# FinalSchematic1_2.net
KiCad netlist of a schematic drawn in EAGLE
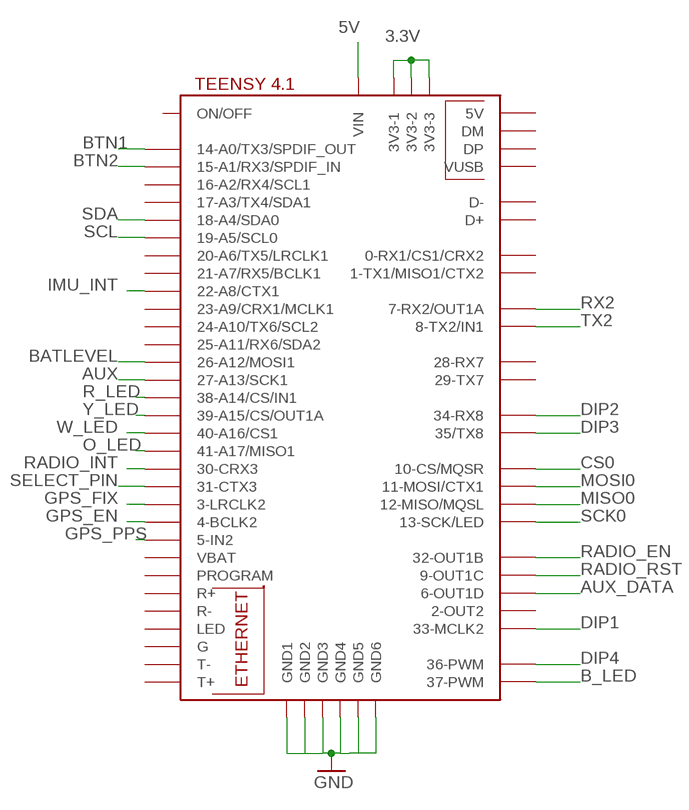
[diagram p0: schematic, sheet 1]
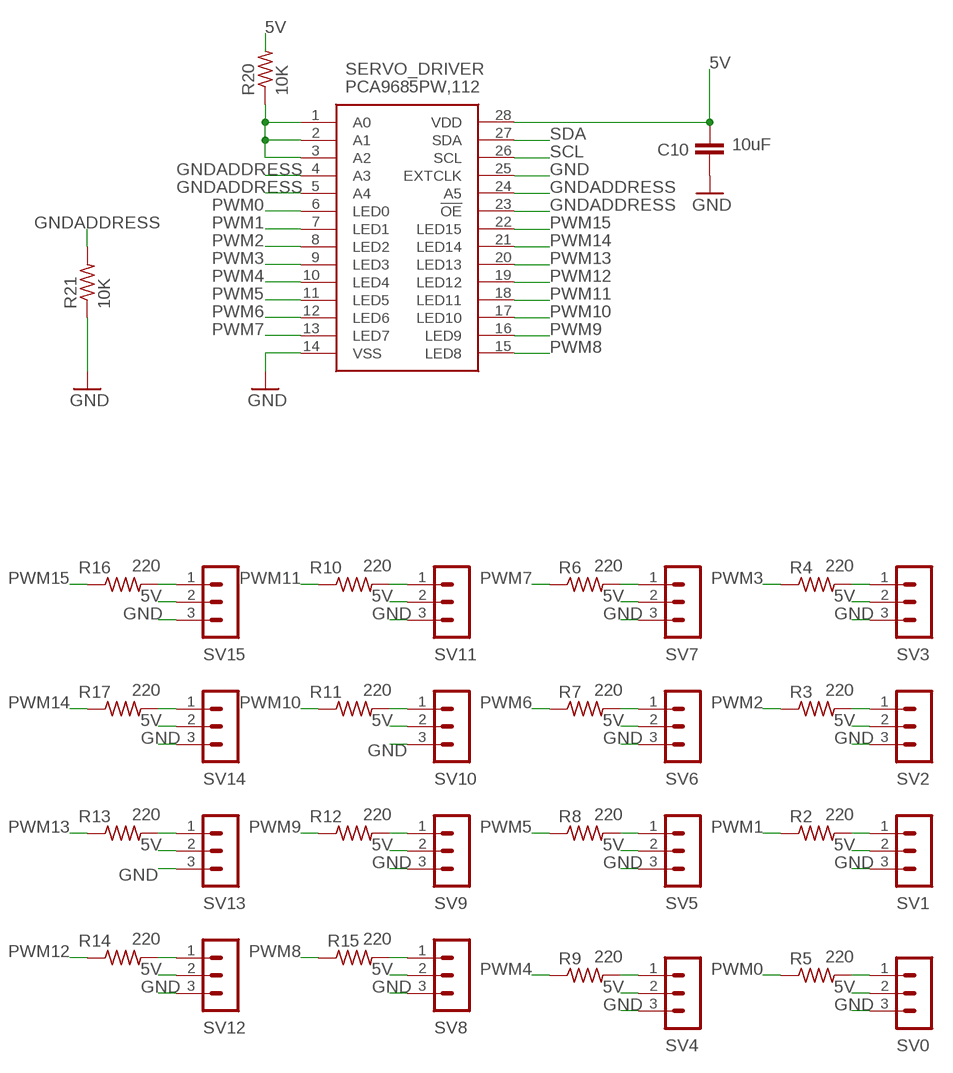
[diagram p1: schematic, sheet 2]
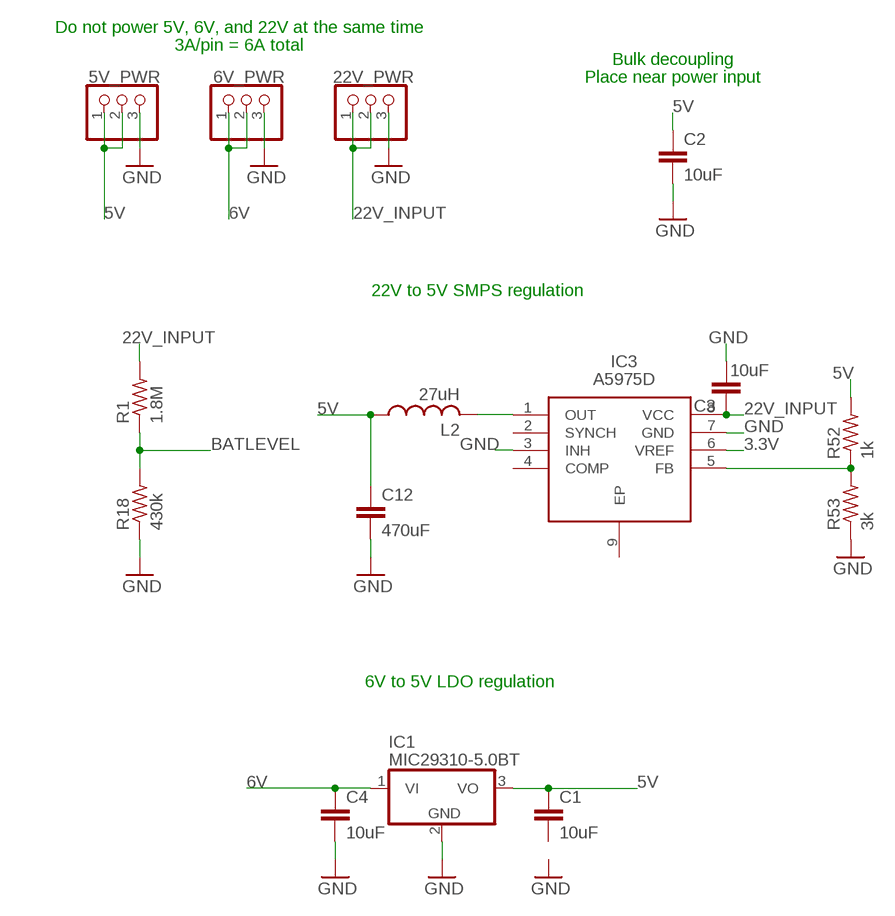
[diagram p2: schematic, sheet 3]
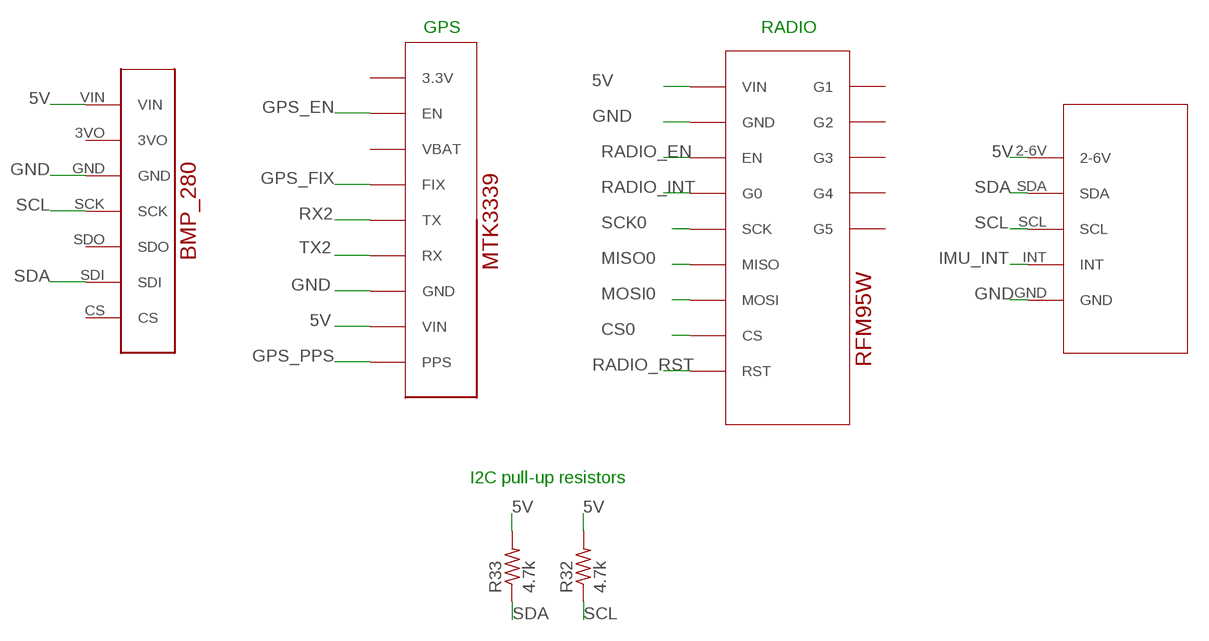
[diagram p3: schematic, sheet 4]
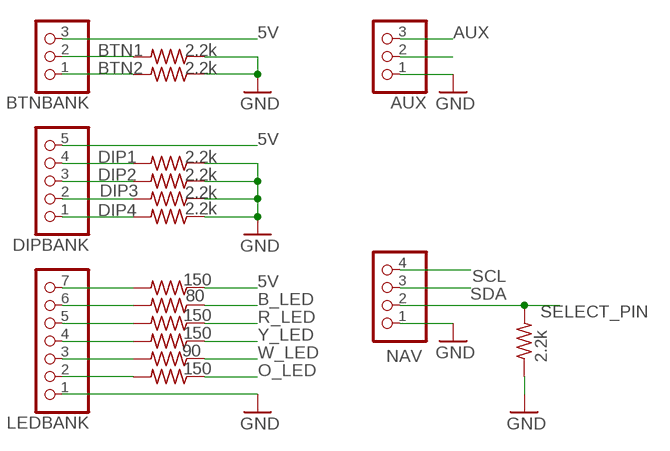
[diagram p4: schematic, sheet 5]
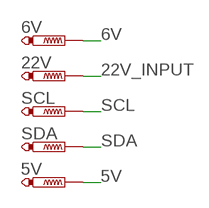
[diagram p5: schematic, sheet 6]

(export (version "E")
  (design (tool "Eeschema 10.0.6"))
  (components
    (comp (ref "TEENSY4.1")
      (value "TEENSY41")
      (footprint "eagle-import:TEENSY41")
      (libsource (lib "eagle-import") (part "TEENSY41"))
    )
    (comp (ref "5V")
      (value "PTR1B1,27")
      (footprint "eagle-import:B1,27")
      (libsource (lib "eagle-import") (part "PTR1B1,27"))
    )
    (comp (ref "6V")
      (value "PTR1B1,27")
      (footprint "eagle-import:B1,27")
      (libsource (lib "eagle-import") (part "PTR1B1,27"))
    )
    (comp (ref "22V")
      (value "PTR1B1,27")
      (footprint "eagle-import:B1,27")
      (libsource (lib "eagle-import") (part "PTR1B1,27"))
    )
    (comp (ref "SCL")
      (value "PTR1B1,27")
      (footprint "eagle-import:B1,27")
      (libsource (lib "eagle-import") (part "PTR1B1,27"))
    )
    (comp (ref "SDA")
      (value "PTR1B1,27")
      (footprint "eagle-import:B1,27")
      (libsource (lib "eagle-import") (part "PTR1B1,27"))
    )
    (comp (ref "AUX")
      (value "PINHD-1X3")
      (footprint "eagle-import:1X03")
      (libsource (lib "eagle-import") (part "PINHD-1X3"))
    )
    (comp (ref "BLUE")
      (value "80")
      (footprint "eagle-import:0204_7")
      (libsource (lib "eagle-import") (part "R-US_0204/7"))
    )
    (comp (ref "BTNBANK")
      (value "PINHD-1X3")
      (footprint "eagle-import:1X03")
      (libsource (lib "eagle-import") (part "PINHD-1X3"))
    )
    (comp (ref "DIPBANK")
      (value "PINHD-1X5")
      (footprint "eagle-import:1X05")
      (libsource (lib "eagle-import") (part "PINHD-1X5"))
    )
    (comp (ref "GREEN")
      (value "150")
      (footprint "eagle-import:0204_7")
      (libsource (lib "eagle-import") (part "R-US_0204/7"))
    )
    (comp (ref "LEDBANK")
      (value "PINHD-1X7")
      (footprint "eagle-import:1X07")
      (libsource (lib "eagle-import") (part "PINHD-1X7"))
    )
    (comp (ref "NAV")
      (value "PINHD-1X4")
      (footprint "eagle-import:1X04")
      (libsource (lib "eagle-import") (part "PINHD-1X4"))
    )
    (comp (ref "ORANGE")
      (value "150")
      (footprint "eagle-import:0204_7")
      (libsource (lib "eagle-import") (part "R-US_0204/7"))
    )
    (comp (ref "R19")
      (value "2.2k")
      (footprint "eagle-import:0204_7")
      (libsource (lib "eagle-import") (part "R-US_0204/7"))
    )
    (comp (ref "R22")
      (value "2.2k")
      (footprint "eagle-import:0204_7")
      (libsource (lib "eagle-import") (part "R-US_0204/7"))
    )
    (comp (ref "R23")
      (value "2.2k")
      (footprint "eagle-import:0204_7")
      (libsource (lib "eagle-import") (part "R-US_0204/7"))
    )
    (comp (ref "R34")
      (value "2.2k")
      (footprint "eagle-import:0204_7")
      (libsource (lib "eagle-import") (part "R-US_0204/7"))
    )
    (comp (ref "R35")
      (value "2.2k")
      (footprint "eagle-import:0204_7")
      (libsource (lib "eagle-import") (part "R-US_0204/7"))
    )
    (comp (ref "R36")
      (value "2.2k")
      (footprint "eagle-import:0204_7")
      (libsource (lib "eagle-import") (part "R-US_0204/7"))
    )
    (comp (ref "R37")
      (value "2.2k")
      (footprint "eagle-import:0204_7")
      (libsource (lib "eagle-import") (part "R-US_0204/7"))
    )
    (comp (ref "RED")
      (value "150")
      (footprint "eagle-import:0204_7")
      (libsource (lib "eagle-import") (part "R-US_0204/7"))
    )
    (comp (ref "WHITE")
      (value "90")
      (footprint "eagle-import:0204_7")
      (libsource (lib "eagle-import") (part "R-US_0204/7"))
    )
    (comp (ref "YELLOW")
      (value "150")
      (footprint "eagle-import:0204_7")
      (libsource (lib "eagle-import") (part "R-US_0204/7"))
    )
    (comp (ref "5V_PWR")
      (value "PINHD-1X3")
      (footprint "eagle-import:1X03")
      (libsource (lib "eagle-import") (part "PINHD-1X3"))
    )
    (comp (ref "6V_PWR")
      (value "PINHD-1X3")
      (footprint "eagle-import:1X03")
      (libsource (lib "eagle-import") (part "PINHD-1X3"))
    )
    (comp (ref "22V_PWR")
      (value "PINHD-1X3")
      (footprint "eagle-import:1X03")
      (libsource (lib "eagle-import") (part "PINHD-1X3"))
    )
    (comp (ref "C1")
      (value "10uF")
      (footprint "eagle-import:C2.5-3")
      (libsource (lib "eagle-import") (part "C2,5-3"))
    )
    (comp (ref "C2")
      (value "10uF")
      (footprint "eagle-import:C2.5-3")
      (libsource (lib "eagle-import") (part "C2,5-3"))
    )
    (comp (ref "C3")
      (value "10uF")
      (footprint "eagle-import:C2.5-3")
      (libsource (lib "eagle-import") (part "C2,5-3"))
    )
    (comp (ref "C4")
      (value "10uF")
      (footprint "eagle-import:C2.5-3")
      (libsource (lib "eagle-import") (part "C2,5-3"))
    )
    (comp (ref "C12")
      (value "470uF")
      (footprint "eagle-import:C2.5-3")
      (libsource (lib "eagle-import") (part "C2,5-3"))
    )
    (comp (ref "IC1")
      (value "MIC29310-5.0BT")
      (footprint "eagle-import:TO220V")
      (libsource (lib "eagle-import") (part "78TV6"))
    )
    (comp (ref "IC3")
      (value "A5975D")
      (footprint "eagle-import:SOIC127P600X170-9N")
      (fields (field (name "MOUSER_PART_NUMBER") "511-A5975D"))
      (libsource (lib "eagle-import") (part "A5975D"))
    )
    (comp (ref "L2")
      (value "27uH")
      (footprint "eagle-import:TFI0307")
      (libsource (lib "eagle-import") (part "L-USTFI0307"))
    )
    (comp (ref "R1")
      (value "1.8M")
      (footprint "eagle-import:0204_7")
      (libsource (lib "eagle-import") (part "R-US_0204/7"))
    )
    (comp (ref "R18")
      (value "430k")
      (footprint "eagle-import:0204_7")
      (libsource (lib "eagle-import") (part "R-US_0204/7"))
    )
    (comp (ref "R52")
      (value "1k")
      (footprint "eagle-import:0204_7")
      (libsource (lib "eagle-import") (part "R-US_0204/7"))
    )
    (comp (ref "R53")
      (value "3k")
      (footprint "eagle-import:0204_7")
      (libsource (lib "eagle-import") (part "R-US_0204/7"))
    )
    (comp (ref "GPSMTK3339")
      (value "ADAFRUIT_MTK3339_GPS")
      (footprint "eagle-import:ADAFRUIT_MTK3339_GPS")
      (libsource (lib "eagle-import") (part "ADAFRUIT_MTK3339_GPS"))
    )
    (comp (ref "IMU")
      (value "ICM20948BREAKOUTDEVICE")
      (footprint "eagle-import:ICM20948BREAKOUT")
      (fields (field (name "SPICEPREFIX") "X"))
      (libsource (lib "eagle-import") (part "ICM20948BREAKOUTDEVICE"))
    )
    (comp (ref "R32")
      (value "4.7k")
      (footprint "eagle-import:0204_7")
      (libsource (lib "eagle-import") (part "R-US_0204/7"))
    )
    (comp (ref "R33")
      (value "4.7k")
      (footprint "eagle-import:0204_7")
      (libsource (lib "eagle-import") (part "R-US_0204/7"))
    )
    (comp (ref "RADIO")
      (value "ADAFRUIT_RFM95W_LORA_RADIO")
      (footprint "eagle-import:ADAFRUIT_RFM95W_LORA_RADIO")
      (libsource (lib "eagle-import") (part "ADAFRUIT_RFM95W_LORA_RADIO"))
    )
    (comp (ref "U1")
      (value "ADAFRUIT_BMP280_BAROMETER")
      (footprint "eagle-import:ADAFRUIT_BMP280_BAROMETER")
      (libsource (lib "eagle-import") (part "ADAFRUIT_BMP280_BAROMETER"))
    )
    (comp (ref "C10")
      (value "10uF")
      (footprint "eagle-import:C2.5-3")
      (libsource (lib "eagle-import") (part "C2,5-3"))
    )
    (comp (ref "R2")
      (value "220")
      (footprint "eagle-import:0204_7")
      (libsource (lib "eagle-import") (part "R-US_0204/7"))
    )
    (comp (ref "R3")
      (value "220")
      (footprint "eagle-import:0204_7")
      (libsource (lib "eagle-import") (part "R-US_0204/7"))
    )
    (comp (ref "R4")
      (value "220")
      (footprint "eagle-import:0204_7")
      (libsource (lib "eagle-import") (part "R-US_0204/7"))
    )
    (comp (ref "R5")
      (value "220")
      (footprint "eagle-import:0204_7")
      (libsource (lib "eagle-import") (part "R-US_0204/7"))
    )
    (comp (ref "R6")
      (value "220")
      (footprint "eagle-import:0204_7")
      (libsource (lib "eagle-import") (part "R-US_0204/7"))
    )
    (comp (ref "R7")
      (value "220")
      (footprint "eagle-import:0204_7")
      (libsource (lib "eagle-import") (part "R-US_0204/7"))
    )
    (comp (ref "R8")
      (value "220")
      (footprint "eagle-import:0204_7")
      (libsource (lib "eagle-import") (part "R-US_0204/7"))
    )
    (comp (ref "R9")
      (value "220")
      (footprint "eagle-import:0204_7")
      (libsource (lib "eagle-import") (part "R-US_0204/7"))
    )
    (comp (ref "R10")
      (value "220")
      (footprint "eagle-import:0204_7")
      (libsource (lib "eagle-import") (part "R-US_0204/7"))
    )
    (comp (ref "R11")
      (value "220")
      (footprint "eagle-import:0204_7")
      (libsource (lib "eagle-import") (part "R-US_0204/7"))
    )
    (comp (ref "R12")
      (value "220")
      (footprint "eagle-import:0204_7")
      (libsource (lib "eagle-import") (part "R-US_0204/7"))
    )
    (comp (ref "R13")
      (value "220")
      (footprint "eagle-import:0204_7")
      (libsource (lib "eagle-import") (part "R-US_0204/7"))
    )
    (comp (ref "R14")
      (value "220")
      (footprint "eagle-import:0204_7")
      (libsource (lib "eagle-import") (part "R-US_0204/7"))
    )
    (comp (ref "R15")
      (value "220")
      (footprint "eagle-import:0204_7")
      (libsource (lib "eagle-import") (part "R-US_0204/7"))
    )
    (comp (ref "R16")
      (value "220")
      (footprint "eagle-import:0204_7")
      (libsource (lib "eagle-import") (part "R-US_0204/7"))
    )
    (comp (ref "R17")
      (value "220")
      (footprint "eagle-import:0204_7")
      (libsource (lib "eagle-import") (part "R-US_0204/7"))
    )
    (comp (ref "R20")
      (value "10K")
      (footprint "eagle-import:0204_7")
      (libsource (lib "eagle-import") (part "R-US_0204/7"))
    )
    (comp (ref "R21")
      (value "10K")
      (footprint "eagle-import:0204_7")
      (libsource (lib "eagle-import") (part "R-US_0204/7"))
    )
    (comp (ref "SERVO_DRIVER")
      (value "PCA9685PW,112")
      (footprint "eagle-import:SOP65P640X110-28N")
      (fields (field (name "MOUSER_PART_NUMBER") "771-PCA9685PW,112"))
      (libsource (lib "eagle-import") (part "PCA9685PW,112"))
    )
    (comp (ref "SV0")
      (value "MA03-1")
      (footprint "eagle-import:MA03-1")
      (libsource (lib "eagle-import") (part "MA03-1"))
    )
    (comp (ref "SV1")
      (value "MA03-1")
      (footprint "eagle-import:MA03-1")
      (libsource (lib "eagle-import") (part "MA03-1"))
    )
    (comp (ref "SV2")
      (value "MA03-1")
      (footprint "eagle-import:MA03-1")
      (libsource (lib "eagle-import") (part "MA03-1"))
    )
    (comp (ref "SV3")
      (value "MA03-1")
      (footprint "eagle-import:MA03-1")
      (libsource (lib "eagle-import") (part "MA03-1"))
    )
    (comp (ref "SV4")
      (value "MA03-1")
      (footprint "eagle-import:MA03-1")
      (libsource (lib "eagle-import") (part "MA03-1"))
    )
    (comp (ref "SV5")
      (value "MA03-1")
      (footprint "eagle-import:MA03-1")
      (libsource (lib "eagle-import") (part "MA03-1"))
    )
    (comp (ref "SV6")
      (value "MA03-1")
      (footprint "eagle-import:MA03-1")
      (libsource (lib "eagle-import") (part "MA03-1"))
    )
    (comp (ref "SV7")
      (value "MA03-1")
      (footprint "eagle-import:MA03-1")
      (libsource (lib "eagle-import") (part "MA03-1"))
    )
    (comp (ref "SV8")
      (value "MA03-1")
      (footprint "eagle-import:MA03-1")
      (libsource (lib "eagle-import") (part "MA03-1"))
    )
    (comp (ref "SV9")
      (value "MA03-1")
      (footprint "eagle-import:MA03-1")
      (libsource (lib "eagle-import") (part "MA03-1"))
    )
    (comp (ref "SV10")
      (value "MA03-1")
      (footprint "eagle-import:MA03-1")
      (libsource (lib "eagle-import") (part "MA03-1"))
    )
    (comp (ref "SV11")
      (value "MA03-1")
      (footprint "eagle-import:MA03-1")
      (libsource (lib "eagle-import") (part "MA03-1"))
    )
    (comp (ref "SV12")
      (value "MA03-1")
      (footprint "eagle-import:MA03-1")
      (libsource (lib "eagle-import") (part "MA03-1"))
    )
    (comp (ref "SV13")
      (value "MA03-1")
      (footprint "eagle-import:MA03-1")
      (libsource (lib "eagle-import") (part "MA03-1"))
    )
    (comp (ref "SV14")
      (value "MA03-1")
      (footprint "eagle-import:MA03-1")
      (libsource (lib "eagle-import") (part "MA03-1"))
    )
    (comp (ref "SV15")
      (value "MA03-1")
      (footprint "eagle-import:MA03-1")
      (libsource (lib "eagle-import") (part "MA03-1"))
    )
  )
  (nets
    (net (code "1") (name "3.3V") (class "Default")
      (node (ref "IC3") (pin "6") (pinfunction "VREF_6") (pintype "bidirectional"))
      (node (ref "TEENSY4.1") (pin "3V3-1") (pinfunction "3V3-1_3V3-1") (pintype "bidirectional"))
      (node (ref "TEENSY4.1") (pin "3V3-2") (pinfunction "3V3-2_3V3-2") (pintype "bidirectional"))
      (node (ref "TEENSY4.1") (pin "3V3-3") (pinfunction "3V3-3_3V3-3") (pintype "bidirectional"))
    )
    (net (code "2") (name "5V") (class "Default")
      (node (ref "5V") (pin "TP") (pinfunction "TP_TP") (pintype "input"))
      (node (ref "5V_PWR") (pin "1") (pinfunction "1_1") (pintype "passive"))
      (node (ref "5V_PWR") (pin "2") (pinfunction "2_2") (pintype "passive"))
      (node (ref "BTNBANK") (pin "3") (pinfunction "3_3") (pintype "passive"))
      (node (ref "C1") (pin "1") (pinfunction "1_1") (pintype "passive"))
      (node (ref "C10") (pin "1") (pinfunction "1_1") (pintype "passive"))
      (node (ref "C12") (pin "1") (pinfunction "1_1") (pintype "passive"))
      (node (ref "C2") (pin "1") (pinfunction "1_1") (pintype "passive"))
      (node (ref "DIPBANK") (pin "5") (pinfunction "5_5") (pintype "passive"))
      (node (ref "GPSMTK3339") (pin "VIN") (pinfunction "VIN_VIN") (pintype "bidirectional"))
      (node (ref "GREEN") (pin "1") (pinfunction "1_1") (pintype "passive"))
      (node (ref "IC1") (pin "3") (pinfunction "VO_3") (pintype "passive"))
      (node (ref "IMU") (pin "2-6V") (pinfunction "2-6V_2-6V") (pintype "bidirectional"))
      (node (ref "L2") (pin "1") (pinfunction "1_1") (pintype "passive"))
      (node (ref "R20") (pin "2") (pinfunction "2_2") (pintype "passive"))
      (node (ref "R32") (pin "2") (pinfunction "2_2") (pintype "passive"))
      (node (ref "R33") (pin "2") (pinfunction "2_2") (pintype "passive"))
      (node (ref "R52") (pin "2") (pinfunction "2_2") (pintype "passive"))
      (node (ref "RADIO") (pin "1") (pinfunction "VIN_1") (pintype "bidirectional"))
      (node (ref "SERVO_DRIVER") (pin "28") (pinfunction "VDD_28") (pintype "bidirectional"))
      (node (ref "SV0") (pin "2") (pinfunction "2_2") (pintype "passive"))
      (node (ref "SV1") (pin "2") (pinfunction "2_2") (pintype "passive"))
      (node (ref "SV10") (pin "2") (pinfunction "2_2") (pintype "passive"))
      (node (ref "SV11") (pin "2") (pinfunction "2_2") (pintype "passive"))
      (node (ref "SV12") (pin "2") (pinfunction "2_2") (pintype "passive"))
      (node (ref "SV13") (pin "2") (pinfunction "2_2") (pintype "passive"))
      (node (ref "SV14") (pin "2") (pinfunction "2_2") (pintype "passive"))
      (node (ref "SV15") (pin "2") (pinfunction "2_2") (pintype "passive"))
      (node (ref "SV2") (pin "2") (pinfunction "2_2") (pintype "passive"))
      (node (ref "SV3") (pin "2") (pinfunction "2_2") (pintype "passive"))
      (node (ref "SV4") (pin "2") (pinfunction "2_2") (pintype "passive"))
      (node (ref "SV5") (pin "2") (pinfunction "2_2") (pintype "passive"))
      (node (ref "SV6") (pin "2") (pinfunction "2_2") (pintype "passive"))
      (node (ref "SV7") (pin "2") (pinfunction "2_2") (pintype "passive"))
      (node (ref "SV8") (pin "2") (pinfunction "2_2") (pintype "passive"))
      (node (ref "SV9") (pin "2") (pinfunction "2_2") (pintype "passive"))
      (node (ref "TEENSY4.1") (pin "VIN") (pinfunction "VIN_VIN") (pintype "bidirectional"))
      (node (ref "U1") (pin "VIN") (pinfunction "VIN_VIN") (pintype "power_in"))
    )
    (net (code "3") (name "6V") (class "Default")
      (node (ref "6V") (pin "TP") (pinfunction "TP_TP") (pintype "input"))
      (node (ref "6V_PWR") (pin "1") (pinfunction "1_1") (pintype "passive"))
      (node (ref "6V_PWR") (pin "2") (pinfunction "2_2") (pintype "passive"))
      (node (ref "C4") (pin "1") (pinfunction "1_1") (pintype "passive"))
      (node (ref "IC1") (pin "1") (pinfunction "VI_1") (pintype "input"))
    )
    (net (code "4") (name "22V_INPUT") (class "Default")
      (node (ref "22V") (pin "TP") (pinfunction "TP_TP") (pintype "input"))
      (node (ref "22V_PWR") (pin "1") (pinfunction "1_1") (pintype "passive"))
      (node (ref "22V_PWR") (pin "2") (pinfunction "2_2") (pintype "passive"))
      (node (ref "C3") (pin "1") (pinfunction "1_1") (pintype "passive"))
      (node (ref "IC3") (pin "8") (pinfunction "VCC_8") (pintype "bidirectional"))
      (node (ref "R1") (pin "2") (pinfunction "2_2") (pintype "passive"))
    )
    (net (code "5") (name "AUX") (class "Default")
      (node (ref "AUX") (pin "3") (pinfunction "3_3") (pintype "passive"))
      (node (ref "TEENSY4.1") (pin "27-A13/SCK1") (pinfunction "27-A13/SCK1_27-A13/SCK1") (pintype "bidirectional"))
    )
    (net (code "6") (name "AUX_DATA") (class "Default")
      (node (ref "TEENSY4.1") (pin "6-OUT1D") (pinfunction "6-OUT1D_6-OUT1D") (pintype "bidirectional"))
    )
    (net (code "7") (name "BATLEVEL") (class "Default")
      (node (ref "R1") (pin "1") (pinfunction "1_1") (pintype "passive"))
      (node (ref "R18") (pin "2") (pinfunction "2_2") (pintype "passive"))
      (node (ref "TEENSY4.1") (pin "26-A12/MOSI1") (pinfunction "26-A12/MOSI1_26-A12/MOSI1") (pintype "bidirectional"))
    )
    (net (code "8") (name "BTN1") (class "Default")
      (node (ref "BTNBANK") (pin "2") (pinfunction "2_2") (pintype "passive"))
      (node (ref "R19") (pin "2") (pinfunction "2_2") (pintype "passive"))
      (node (ref "TEENSY4.1") (pin "14-A0/TX3/SPDIF_OUT") (pinfunction "14-A0/TX3/SPDIF_OUT_14-A0/TX3/SPDIF_OUT") (pintype "bidirectional"))
    )
    (net (code "9") (name "BTN2") (class "Default")
      (node (ref "BTNBANK") (pin "1") (pinfunction "1_1") (pintype "passive"))
      (node (ref "R22") (pin "2") (pinfunction "2_2") (pintype "passive"))
      (node (ref "TEENSY4.1") (pin "15-A1/RX3/SPDIF_IN") (pinfunction "15-A1/RX3/SPDIF_IN_15-A1/RX3/SPDIF_IN") (pintype "bidirectional"))
    )
    (net (code "10") (name "B_LED") (class "Default")
      (node (ref "BLUE") (pin "1") (pinfunction "1_1") (pintype "passive"))
      (node (ref "TEENSY4.1") (pin "37-PWM") (pinfunction "37-PWM_37-PWM") (pintype "bidirectional"))
    )
    (net (code "11") (name "CS0") (class "Default")
      (node (ref "RADIO") (pin "8") (pinfunction "CS_8") (pintype "bidirectional"))
      (node (ref "TEENSY4.1") (pin "10-CS\\MQSR") (pinfunction "10-CS/MQSR_10-CS\\MQSR") (pintype "bidirectional"))
    )
    (net (code "12") (name "DIP1") (class "Default")
      (node (ref "DIPBANK") (pin "4") (pinfunction "4_4") (pintype "passive"))
      (node (ref "R37") (pin "2") (pinfunction "2_2") (pintype "passive"))
      (node (ref "TEENSY4.1") (pin "33-MCLK2") (pinfunction "33-MCLK2_33-MCLK2") (pintype "bidirectional"))
    )
    (net (code "13") (name "DIP2") (class "Default")
      (node (ref "DIPBANK") (pin "3") (pinfunction "3_3") (pintype "passive"))
      (node (ref "R36") (pin "2") (pinfunction "2_2") (pintype "passive"))
      (node (ref "TEENSY4.1") (pin "34-RX8") (pinfunction "34-RX8_34-RX8") (pintype "bidirectional"))
    )
    (net (code "14") (name "DIP3") (class "Default")
      (node (ref "DIPBANK") (pin "2") (pinfunction "2_2") (pintype "passive"))
      (node (ref "R34") (pin "2") (pinfunction "2_2") (pintype "passive"))
      (node (ref "TEENSY4.1") (pin "35-TX8") (pinfunction "35/TX8_35-TX8") (pintype "bidirectional"))
    )
    (net (code "15") (name "DIP4") (class "Default")
      (node (ref "DIPBANK") (pin "1") (pinfunction "1_1") (pintype "passive"))
      (node (ref "R35") (pin "2") (pinfunction "2_2") (pintype "passive"))
      (node (ref "TEENSY4.1") (pin "36-PWM") (pinfunction "36-PWM_36-PWM") (pintype "bidirectional"))
    )
    (net (code "16") (name "GND") (class "Default")
      (node (ref "22V_PWR") (pin "3") (pinfunction "3_3") (pintype "passive"))
      (node (ref "5V_PWR") (pin "3") (pinfunction "3_3") (pintype "passive"))
      (node (ref "6V_PWR") (pin "3") (pinfunction "3_3") (pintype "passive"))
      (node (ref "AUX") (pin "1") (pinfunction "1_1") (pintype "passive"))
      (node (ref "C10") (pin "2") (pinfunction "2_2") (pintype "passive"))
      (node (ref "C12") (pin "2") (pinfunction "2_2") (pintype "passive"))
      (node (ref "C2") (pin "2") (pinfunction "2_2") (pintype "passive"))
      (node (ref "C3") (pin "2") (pinfunction "2_2") (pintype "passive"))
      (node (ref "C4") (pin "2") (pinfunction "2_2") (pintype "passive"))
      (node (ref "GPSMTK3339") (pin "GND") (pinfunction "GND_GND") (pintype "bidirectional"))
      (node (ref "IC1") (pin "2") (pinfunction "GND_2") (pintype "passive"))
      (node (ref "IC3") (pin "3") (pinfunction "INH_3") (pintype "bidirectional"))
      (node (ref "IC3") (pin "7") (pinfunction "GND_7") (pintype "bidirectional"))
      (node (ref "IMU") (pin "GND") (pinfunction "GND_GND") (pintype "bidirectional"))
      (node (ref "LEDBANK") (pin "1") (pinfunction "1_1") (pintype "passive"))
      (node (ref "NAV") (pin "1") (pinfunction "1_1") (pintype "passive"))
      (node (ref "R18") (pin "1") (pinfunction "1_1") (pintype "passive"))
      (node (ref "R19") (pin "1") (pinfunction "1_1") (pintype "passive"))
      (node (ref "R21") (pin "1") (pinfunction "1_1") (pintype "passive"))
      (node (ref "R22") (pin "1") (pinfunction "1_1") (pintype "passive"))
      (node (ref "R23") (pin "1") (pinfunction "1_1") (pintype "passive"))
      (node (ref "R34") (pin "1") (pinfunction "1_1") (pintype "passive"))
      (node (ref "R35") (pin "1") (pinfunction "1_1") (pintype "passive"))
      (node (ref "R36") (pin "1") (pinfunction "1_1") (pintype "passive"))
      (node (ref "R37") (pin "1") (pinfunction "1_1") (pintype "passive"))
      (node (ref "R53") (pin "1") (pinfunction "1_1") (pintype "passive"))
      (node (ref "RADIO") (pin "2") (pinfunction "GND_2") (pintype "bidirectional"))
      (node (ref "SERVO_DRIVER") (pin "14") (pinfunction "VSS_14") (pintype "bidirectional"))
      (node (ref "SERVO_DRIVER") (pin "25") (pinfunction "EXTCLK_25") (pintype "bidirectional"))
      (node (ref "SV0") (pin "3") (pinfunction "3_3") (pintype "passive"))
      (node (ref "SV1") (pin "3") (pinfunction "3_3") (pintype "passive"))
      (node (ref "SV10") (pin "3") (pinfunction "3_3") (pintype "passive"))
      (node (ref "SV11") (pin "3") (pinfunction "3_3") (pintype "passive"))
      (node (ref "SV12") (pin "3") (pinfunction "3_3") (pintype "passive"))
      (node (ref "SV13") (pin "3") (pinfunction "3_3") (pintype "passive"))
      (node (ref "SV14") (pin "3") (pinfunction "3_3") (pintype "passive"))
      (node (ref "SV15") (pin "3") (pinfunction "3_3") (pintype "passive"))
      (node (ref "SV2") (pin "3") (pinfunction "3_3") (pintype "passive"))
      (node (ref "SV3") (pin "3") (pinfunction "3_3") (pintype "passive"))
      (node (ref "SV4") (pin "3") (pinfunction "3_3") (pintype "passive"))
      (node (ref "SV5") (pin "3") (pinfunction "3_3") (pintype "passive"))
      (node (ref "SV6") (pin "3") (pinfunction "3_3") (pintype "passive"))
      (node (ref "SV7") (pin "3") (pinfunction "3_3") (pintype "passive"))
      (node (ref "SV8") (pin "3") (pinfunction "3_3") (pintype "passive"))
      (node (ref "SV9") (pin "3") (pinfunction "3_3") (pintype "passive"))
      (node (ref "TEENSY4.1") (pin "GND1") (pinfunction "GND1_GND1") (pintype "bidirectional"))
      (node (ref "TEENSY4.1") (pin "GND2") (pinfunction "GND2_GND2") (pintype "bidirectional"))
      (node (ref "TEENSY4.1") (pin "GND3") (pinfunction "GND3_GND3") (pintype "bidirectional"))
      (node (ref "TEENSY4.1") (pin "GND4") (pinfunction "GND4_GND4") (pintype "bidirectional"))
      (node (ref "TEENSY4.1") (pin "GND5") (pinfunction "GND5_GND5") (pintype "bidirectional"))
      (node (ref "TEENSY4.1") (pin "GND6") (pinfunction "GND6_GND6") (pintype "bidirectional"))
      (node (ref "U1") (pin "GND") (pinfunction "GND_GND") (pintype "power_in"))
    )
    (net (code "17") (name "GNDADDRESS") (class "Default")
      (node (ref "R21") (pin "2") (pinfunction "2_2") (pintype "passive"))
      (node (ref "SERVO_DRIVER") (pin "23") (pinfunction "~{OE}_23") (pintype "bidirectional"))
      (node (ref "SERVO_DRIVER") (pin "24") (pinfunction "A5_24") (pintype "bidirectional"))
      (node (ref "SERVO_DRIVER") (pin "4") (pinfunction "A3_4") (pintype "bidirectional"))
      (node (ref "SERVO_DRIVER") (pin "5") (pinfunction "A4_5") (pintype "bidirectional"))
    )
    (net (code "18") (name "GPS_EN") (class "Default")
      (node (ref "GPSMTK3339") (pin "EN") (pinfunction "EN_EN") (pintype "bidirectional"))
      (node (ref "TEENSY4.1") (pin "4-BCLK2") (pinfunction "4-BCLK2_4-BCLK2") (pintype "bidirectional"))
    )
    (net (code "19") (name "GPS_FIX") (class "Default")
      (node (ref "GPSMTK3339") (pin "FIX") (pinfunction "FIX_FIX") (pintype "bidirectional"))
      (node (ref "TEENSY4.1") (pin "3-LRCLK2") (pinfunction "3-LRCLK2_3-LRCLK2") (pintype "bidirectional"))
    )
    (net (code "20") (name "GPS_PPS") (class "Default")
      (node (ref "GPSMTK3339") (pin "PPS") (pinfunction "PPS_PPS") (pintype "bidirectional"))
      (node (ref "TEENSY4.1") (pin "5-IN2") (pinfunction "5-IN2_5-IN2") (pintype "bidirectional"))
    )
    (net (code "21") (name "IMU_INT") (class "Default")
      (node (ref "IMU") (pin "INT") (pinfunction "INT_INT") (pintype "bidirectional"))
      (node (ref "TEENSY4.1") (pin "22-A8/CTX1") (pinfunction "22-A8/CTX1_22-A8/CTX1") (pintype "bidirectional"))
    )
    (net (code "22") (name "MISO0") (class "Default")
      (node (ref "RADIO") (pin "6") (pinfunction "MISO_6") (pintype "bidirectional"))
      (node (ref "TEENSY4.1") (pin "12-MISO/MQSL") (pinfunction "12-MISO/MQSL_12-MISO/MQSL") (pintype "bidirectional"))
    )
    (net (code "23") (name "MOSI0") (class "Default")
      (node (ref "RADIO") (pin "7") (pinfunction "MOSI_7") (pintype "bidirectional"))
      (node (ref "TEENSY4.1") (pin "11-MOSI/CTX1") (pinfunction "11-MOSI/CTX1_11-MOSI/CTX1") (pintype "bidirectional"))
    )
    (net (code "24") (name "Net-(BLUE-Pad2)") (class "Default")
      (node (ref "BLUE") (pin "2") (pinfunction "2_2") (pintype "passive"))
      (node (ref "LEDBANK") (pin "6") (pinfunction "6_6") (pintype "passive"))
    )
    (net (code "25") (name "Net-(GREEN-Pad2)") (class "Default")
      (node (ref "GREEN") (pin "2") (pinfunction "2_2") (pintype "passive"))
      (node (ref "LEDBANK") (pin "7") (pinfunction "7_7") (pintype "passive"))
    )
    (net (code "26") (name "Net-(IC3-FB)") (class "Default")
      (node (ref "IC3") (pin "5") (pinfunction "FB_5") (pintype "bidirectional"))
      (node (ref "R52") (pin "1") (pinfunction "1_1") (pintype "passive"))
      (node (ref "R53") (pin "2") (pinfunction "2_2") (pintype "passive"))
    )
    (net (code "27") (name "Net-(IC3-OUT)") (class "Default")
      (node (ref "IC3") (pin "1") (pinfunction "OUT_1") (pintype "bidirectional"))
      (node (ref "L2") (pin "2") (pinfunction "2_2") (pintype "passive"))
    )
    (net (code "28") (name "Net-(LEDBANK-Pad2)") (class "Default")
      (node (ref "LEDBANK") (pin "2") (pinfunction "2_2") (pintype "passive"))
      (node (ref "ORANGE") (pin "2") (pinfunction "2_2") (pintype "passive"))
    )
    (net (code "29") (name "Net-(LEDBANK-Pad3)") (class "Default")
      (node (ref "LEDBANK") (pin "3") (pinfunction "3_3") (pintype "passive"))
      (node (ref "WHITE") (pin "2") (pinfunction "2_2") (pintype "passive"))
    )
    (net (code "30") (name "Net-(LEDBANK-Pad4)") (class "Default")
      (node (ref "LEDBANK") (pin "4") (pinfunction "4_4") (pintype "passive"))
      (node (ref "YELLOW") (pin "2") (pinfunction "2_2") (pintype "passive"))
    )
    (net (code "31") (name "Net-(LEDBANK-Pad5)") (class "Default")
      (node (ref "LEDBANK") (pin "5") (pinfunction "5_5") (pintype "passive"))
      (node (ref "RED") (pin "2") (pinfunction "2_2") (pintype "passive"))
    )
    (net (code "32") (name "Net-(R2-Pad2)") (class "Default")
      (node (ref "R2") (pin "2") (pinfunction "2_2") (pintype "passive"))
      (node (ref "SV1") (pin "1") (pinfunction "1_1") (pintype "passive"))
    )
    (net (code "33") (name "Net-(R3-Pad2)") (class "Default")
      (node (ref "R3") (pin "2") (pinfunction "2_2") (pintype "passive"))
      (node (ref "SV2") (pin "1") (pinfunction "1_1") (pintype "passive"))
    )
    (net (code "34") (name "Net-(R4-Pad2)") (class "Default")
      (node (ref "R4") (pin "2") (pinfunction "2_2") (pintype "passive"))
      (node (ref "SV3") (pin "1") (pinfunction "1_1") (pintype "passive"))
    )
    (net (code "35") (name "Net-(R5-Pad2)") (class "Default")
      (node (ref "R5") (pin "2") (pinfunction "2_2") (pintype "passive"))
      (node (ref "SV0") (pin "1") (pinfunction "1_1") (pintype "passive"))
    )
    (net (code "36") (name "Net-(R6-Pad2)") (class "Default")
      (node (ref "R6") (pin "2") (pinfunction "2_2") (pintype "passive"))
      (node (ref "SV7") (pin "1") (pinfunction "1_1") (pintype "passive"))
    )
    (net (code "37") (name "Net-(R7-Pad2)") (class "Default")
      (node (ref "R7") (pin "2") (pinfunction "2_2") (pintype "passive"))
      (node (ref "SV6") (pin "1") (pinfunction "1_1") (pintype "passive"))
    )
    (net (code "38") (name "Net-(R8-Pad2)") (class "Default")
      (node (ref "R8") (pin "2") (pinfunction "2_2") (pintype "passive"))
      (node (ref "SV5") (pin "1") (pinfunction "1_1") (pintype "passive"))
    )
    (net (code "39") (name "Net-(R9-Pad2)") (class "Default")
      (node (ref "R9") (pin "2") (pinfunction "2_2") (pintype "passive"))
      (node (ref "SV4") (pin "1") (pinfunction "1_1") (pintype "passive"))
    )
    (net (code "40") (name "Net-(R10-Pad2)") (class "Default")
      (node (ref "R10") (pin "2") (pinfunction "2_2") (pintype "passive"))
      (node (ref "SV11") (pin "1") (pinfunction "1_1") (pintype "passive"))
    )
    (net (code "41") (name "Net-(R11-Pad2)") (class "Default")
      (node (ref "R11") (pin "2") (pinfunction "2_2") (pintype "passive"))
      (node (ref "SV10") (pin "1") (pinfunction "1_1") (pintype "passive"))
    )
    (net (code "42") (name "Net-(R12-Pad2)") (class "Default")
      (node (ref "R12") (pin "2") (pinfunction "2_2") (pintype "passive"))
      (node (ref "SV9") (pin "1") (pinfunction "1_1") (pintype "passive"))
    )
    (net (code "43") (name "Net-(R13-Pad2)") (class "Default")
      (node (ref "R13") (pin "2") (pinfunction "2_2") (pintype "passive"))
      (node (ref "SV13") (pin "1") (pinfunction "1_1") (pintype "passive"))
    )
    (net (code "44") (name "Net-(R14-Pad2)") (class "Default")
      (node (ref "R14") (pin "2") (pinfunction "2_2") (pintype "passive"))
      (node (ref "SV12") (pin "1") (pinfunction "1_1") (pintype "passive"))
    )
    (net (code "45") (name "Net-(R15-Pad2)") (class "Default")
      (node (ref "R15") (pin "2") (pinfunction "2_2") (pintype "passive"))
      (node (ref "SV8") (pin "1") (pinfunction "1_1") (pintype "passive"))
    )
    (net (code "46") (name "Net-(R16-Pad2)") (class "Default")
      (node (ref "R16") (pin "2") (pinfunction "2_2") (pintype "passive"))
      (node (ref "SV15") (pin "1") (pinfunction "1_1") (pintype "passive"))
    )
    (net (code "47") (name "Net-(R17-Pad2)") (class "Default")
      (node (ref "R17") (pin "2") (pinfunction "2_2") (pintype "passive"))
      (node (ref "SV14") (pin "1") (pinfunction "1_1") (pintype "passive"))
    )
    (net (code "48") (name "Net-(SERVO_DRIVER-A0)") (class "Default")
      (node (ref "R20") (pin "1") (pinfunction "1_1") (pintype "passive"))
      (node (ref "SERVO_DRIVER") (pin "1") (pinfunction "A0_1") (pintype "bidirectional"))
      (node (ref "SERVO_DRIVER") (pin "2") (pinfunction "A1_2") (pintype "bidirectional"))
      (node (ref "SERVO_DRIVER") (pin "3") (pinfunction "A2_3") (pintype "bidirectional"))
    )
    (net (code "49") (name "O_LED") (class "Default")
      (node (ref "ORANGE") (pin "1") (pinfunction "1_1") (pintype "passive"))
      (node (ref "TEENSY4.1") (pin "41-A17/MISO1") (pinfunction "41-A17/MISO1_41-A17/MISO1") (pintype "bidirectional"))
    )
    (net (code "50") (name "PWM0") (class "Default")
      (node (ref "R5") (pin "1") (pinfunction "1_1") (pintype "passive"))
      (node (ref "SERVO_DRIVER") (pin "6") (pinfunction "LED0_6") (pintype "bidirectional"))
    )
    (net (code "51") (name "PWM1") (class "Default")
      (node (ref "R2") (pin "1") (pinfunction "1_1") (pintype "passive"))
      (node (ref "SERVO_DRIVER") (pin "7") (pinfunction "LED1_7") (pintype "bidirectional"))
    )
    (net (code "52") (name "PWM2") (class "Default")
      (node (ref "R3") (pin "1") (pinfunction "1_1") (pintype "passive"))
      (node (ref "SERVO_DRIVER") (pin "8") (pinfunction "LED2_8") (pintype "bidirectional"))
    )
    (net (code "53") (name "PWM3") (class "Default")
      (node (ref "R4") (pin "1") (pinfunction "1_1") (pintype "passive"))
      (node (ref "SERVO_DRIVER") (pin "9") (pinfunction "LED3_9") (pintype "bidirectional"))
    )
    (net (code "54") (name "PWM4") (class "Default")
      (node (ref "R9") (pin "1") (pinfunction "1_1") (pintype "passive"))
      (node (ref "SERVO_DRIVER") (pin "10") (pinfunction "LED4_10") (pintype "bidirectional"))
    )
    (net (code "55") (name "PWM5") (class "Default")
      (node (ref "R8") (pin "1") (pinfunction "1_1") (pintype "passive"))
      (node (ref "SERVO_DRIVER") (pin "11") (pinfunction "LED5_11") (pintype "bidirectional"))
    )
    (net (code "56") (name "PWM6") (class "Default")
      (node (ref "R7") (pin "1") (pinfunction "1_1") (pintype "passive"))
      (node (ref "SERVO_DRIVER") (pin "12") (pinfunction "LED6_12") (pintype "bidirectional"))
    )
    (net (code "57") (name "PWM7") (class "Default")
      (node (ref "R6") (pin "1") (pinfunction "1_1") (pintype "passive"))
      (node (ref "SERVO_DRIVER") (pin "13") (pinfunction "LED7_13") (pintype "bidirectional"))
    )
    (net (code "58") (name "PWM8") (class "Default")
      (node (ref "R15") (pin "1") (pinfunction "1_1") (pintype "passive"))
      (node (ref "SERVO_DRIVER") (pin "15") (pinfunction "LED8_15") (pintype "bidirectional"))
    )
    (net (code "59") (name "PWM9") (class "Default")
      (node (ref "R12") (pin "1") (pinfunction "1_1") (pintype "passive"))
      (node (ref "SERVO_DRIVER") (pin "16") (pinfunction "LED9_16") (pintype "bidirectional"))
    )
    (net (code "60") (name "PWM10") (class "Default")
      (node (ref "R11") (pin "1") (pinfunction "1_1") (pintype "passive"))
      (node (ref "SERVO_DRIVER") (pin "17") (pinfunction "LED10_17") (pintype "bidirectional"))
    )
    (net (code "61") (name "PWM11") (class "Default")
      (node (ref "R10") (pin "1") (pinfunction "1_1") (pintype "passive"))
      (node (ref "SERVO_DRIVER") (pin "18") (pinfunction "LED11_18") (pintype "bidirectional"))
    )
    (net (code "62") (name "PWM12") (class "Default")
      (node (ref "R14") (pin "1") (pinfunction "1_1") (pintype "passive"))
      (node (ref "SERVO_DRIVER") (pin "19") (pinfunction "LED12_19") (pintype "bidirectional"))
    )
    (net (code "63") (name "PWM13") (class "Default")
      (node (ref "R13") (pin "1") (pinfunction "1_1") (pintype "passive"))
      (node (ref "SERVO_DRIVER") (pin "20") (pinfunction "LED13_20") (pintype "bidirectional"))
    )
    (net (code "64") (name "PWM14") (class "Default")
      (node (ref "R17") (pin "1") (pinfunction "1_1") (pintype "passive"))
      (node (ref "SERVO_DRIVER") (pin "21") (pinfunction "LED14_21") (pintype "bidirectional"))
    )
    (net (code "65") (name "PWM15") (class "Default")
      (node (ref "R16") (pin "1") (pinfunction "1_1") (pintype "passive"))
      (node (ref "SERVO_DRIVER") (pin "22") (pinfunction "LED15_22") (pintype "bidirectional"))
    )
    (net (code "66") (name "RADIO_EN") (class "Default")
      (node (ref "RADIO") (pin "3") (pinfunction "EN_3") (pintype "bidirectional"))
      (node (ref "TEENSY4.1") (pin "32-OUT1B") (pinfunction "32-OUT1B_32-OUT1B") (pintype "bidirectional"))
    )
    (net (code "67") (name "RADIO_INT") (class "Default")
      (node (ref "RADIO") (pin "4") (pinfunction "G0_4") (pintype "bidirectional"))
      (node (ref "TEENSY4.1") (pin "30-CRX3") (pinfunction "30-CRX3_30-CRX3") (pintype "bidirectional"))
    )
    (net (code "68") (name "RADIO_RST") (class "Default")
      (node (ref "RADIO") (pin "9") (pinfunction "RST_9") (pintype "bidirectional"))
      (node (ref "TEENSY4.1") (pin "9-OUT1C") (pinfunction "9-OUT1C_9-OUT1C") (pintype "bidirectional"))
    )
    (net (code "69") (name "RX2") (class "Default")
      (node (ref "GPSMTK3339") (pin "TX") (pinfunction "TX_TX") (pintype "bidirectional"))
      (node (ref "TEENSY4.1") (pin "7-RX2/OUT1A") (pinfunction "7-RX2/OUT1A_7-RX2/OUT1A") (pintype "bidirectional"))
    )
    (net (code "70") (name "R_LED") (class "Default")
      (node (ref "RED") (pin "1") (pinfunction "1_1") (pintype "passive"))
      (node (ref "TEENSY4.1") (pin "38-A14/CS/IN1") (pinfunction "38-A14/CS/IN1_38-A14/CS/IN1") (pintype "bidirectional"))
    )
    (net (code "71") (name "SCK0") (class "Default")
      (node (ref "RADIO") (pin "5") (pinfunction "SCK_5") (pintype "bidirectional"))
      (node (ref "TEENSY4.1") (pin "13-SCK/LED") (pinfunction "13-SCK/LED_13-SCK/LED") (pintype "bidirectional"))
    )
    (net (code "72") (name "SCL") (class "Default")
      (node (ref "IMU") (pin "SCL") (pinfunction "SCL_SCL") (pintype "bidirectional"))
      (node (ref "NAV") (pin "4") (pinfunction "4_4") (pintype "passive"))
      (node (ref "R32") (pin "1") (pinfunction "1_1") (pintype "passive"))
      (node (ref "SCL") (pin "TP") (pinfunction "TP_TP") (pintype "input"))
      (node (ref "SERVO_DRIVER") (pin "26") (pinfunction "SCL_26") (pintype "bidirectional"))
      (node (ref "TEENSY4.1") (pin "19-A5/SCL0") (pinfunction "19-A5/SCL0_19-A5/SCL0") (pintype "bidirectional"))
      (node (ref "U1") (pin "SCK") (pinfunction "SCK_SCK") (pintype "bidirectional"))
    )
    (net (code "73") (name "SDA") (class "Default")
      (node (ref "IMU") (pin "SDA") (pinfunction "SDA_SDA") (pintype "bidirectional"))
      (node (ref "NAV") (pin "3") (pinfunction "3_3") (pintype "passive"))
      (node (ref "R33") (pin "1") (pinfunction "1_1") (pintype "passive"))
      (node (ref "SDA") (pin "TP") (pinfunction "TP_TP") (pintype "input"))
      (node (ref "SERVO_DRIVER") (pin "27") (pinfunction "SDA_27") (pintype "bidirectional"))
      (node (ref "TEENSY4.1") (pin "18-A4/SDA0") (pinfunction "18-A4/SDA0_18-A4/SDA0") (pintype "bidirectional"))
      (node (ref "U1") (pin "SDI") (pinfunction "SDI_SDI") (pintype "bidirectional"))
    )
    (net (code "74") (name "SELECT_PIN") (class "Default")
      (node (ref "NAV") (pin "2") (pinfunction "2_2") (pintype "passive"))
      (node (ref "R23") (pin "2") (pinfunction "2_2") (pintype "passive"))
      (node (ref "TEENSY4.1") (pin "31-CTX3") (pinfunction "31-CTX3_31-CTX3") (pintype "bidirectional"))
    )
    (net (code "75") (name "TX2") (class "Default")
      (node (ref "GPSMTK3339") (pin "RX") (pinfunction "RX_RX") (pintype "bidirectional"))
      (node (ref "TEENSY4.1") (pin "8-TX2/IN1") (pinfunction "8-TX2/IN1_8-TX2/IN1") (pintype "bidirectional"))
    )
    (net (code "76") (name "W_LED") (class "Default")
      (node (ref "TEENSY4.1") (pin "40-A16/CS1") (pinfunction "40-A16/CS1_40-A16/CS1") (pintype "bidirectional"))
      (node (ref "WHITE") (pin "1") (pinfunction "1_1") (pintype "passive"))
    )
    (net (code "77") (name "Y_LED") (class "Default")
      (node (ref "TEENSY4.1") (pin "39-A15/CS/OUT1A") (pinfunction "39-A15/CS/OUT1A_39-A15/CS/OUT1A") (pintype "bidirectional"))
      (node (ref "YELLOW") (pin "1") (pinfunction "1_1") (pintype "passive"))
    )
    (net (code "78") (name "unconnected-(AUX-Pad2)") (class "Default")
      (node (ref "AUX") (pin "2") (pinfunction "2_2") (pintype "passive"))
    )
    (net (code "79") (name "unconnected-(C1-Pad2)") (class "Default")
      (node (ref "C1") (pin "2") (pinfunction "2_2") (pintype "passive"))
    )
    (net (code "80") (name "unconnected-(GPSMTK3339-Pad3.3V)") (class "Default")
      (node (ref "GPSMTK3339") (pin "3.3V") (pinfunction "3.3V_3.3V") (pintype "bidirectional"))
    )
    (net (code "81") (name "unconnected-(GPSMTK3339-PadVBAT)") (class "Default")
      (node (ref "GPSMTK3339") (pin "VBAT") (pinfunction "VBAT_VBAT") (pintype "bidirectional"))
    )
    (net (code "82") (name "unconnected-(IC3-COMP-Pad4)") (class "Default")
      (node (ref "IC3") (pin "4") (pinfunction "COMP_4") (pintype "bidirectional"))
    )
    (net (code "83") (name "unconnected-(IC3-EP-Pad9)") (class "Default")
      (node (ref "IC3") (pin "9") (pinfunction "EP_9") (pintype "bidirectional"))
    )
    (net (code "84") (name "unconnected-(IC3-SYNCH-Pad2)") (class "Default")
      (node (ref "IC3") (pin "2") (pinfunction "SYNCH_2") (pintype "bidirectional"))
    )
    (net (code "85") (name "unconnected-(RADIO-G1-Pad10)") (class "Default")
      (node (ref "RADIO") (pin "10") (pinfunction "G1_10") (pintype "bidirectional"))
    )
    (net (code "86") (name "unconnected-(RADIO-G2-Pad11)") (class "Default")
      (node (ref "RADIO") (pin "11") (pinfunction "G2_11") (pintype "bidirectional"))
    )
    (net (code "87") (name "unconnected-(RADIO-G3-Pad12)") (class "Default")
      (node (ref "RADIO") (pin "12") (pinfunction "G3_12") (pintype "bidirectional"))
    )
    (net (code "88") (name "unconnected-(RADIO-G4-Pad13)") (class "Default")
      (node (ref "RADIO") (pin "13") (pinfunction "G4_13") (pintype "bidirectional"))
    )
    (net (code "89") (name "unconnected-(RADIO-G5-Pad14)") (class "Default")
      (node (ref "RADIO") (pin "14") (pinfunction "G5_14") (pintype "bidirectional"))
    )
    (net (code "90") (name "unconnected-(TEENSY4.1-5V-Pad+5V)") (class "Default")
      (node (ref "TEENSY4.1") (pin "+5V") (pinfunction "5V_+5V") (pintype "bidirectional"))
    )
    (net (code "91") (name "unconnected-(TEENSY4.1-Pad0-RX1{slash}CS1{slash}CRX2)") (class "Default")
      (node (ref "TEENSY4.1") (pin "0-RX1/CS1/CRX2") (pinfunction "0-RX1/CS1/CRX2_0-RX1/CS1/CRX2") (pintype "bidirectional"))
    )
    (net (code "92") (name "unconnected-(TEENSY4.1-Pad1-TX1{slash}MISO1{slash}CTX2)") (class "Default")
      (node (ref "TEENSY4.1") (pin "1-TX1/MISO1/CTX2") (pinfunction "1-TX1/MISO1/CTX2_1-TX1/MISO1/CTX2") (pintype "bidirectional"))
    )
    (net (code "93") (name "unconnected-(TEENSY4.1-Pad2-OUT2)") (class "Default")
      (node (ref "TEENSY4.1") (pin "2-OUT2") (pinfunction "2-OUT2_2-OUT2") (pintype "bidirectional"))
    )
    (net (code "94") (name "unconnected-(TEENSY4.1-Pad16-A2{slash}RX4{slash}SCL1)") (class "Default")
      (node (ref "TEENSY4.1") (pin "16-A2/RX4/SCL1") (pinfunction "16-A2/RX4/SCL1_16-A2/RX4/SCL1") (pintype "bidirectional"))
    )
    (net (code "95") (name "unconnected-(TEENSY4.1-Pad17-A3{slash}TX4{slash}SDA1)") (class "Default")
      (node (ref "TEENSY4.1") (pin "17-A3/TX4/SDA1") (pinfunction "17-A3/TX4/SDA1_17-A3/TX4/SDA1") (pintype "bidirectional"))
    )
    (net (code "96") (name "unconnected-(TEENSY4.1-Pad20-A6{slash}TX5{slash}LRCLK1)") (class "Default")
      (node (ref "TEENSY4.1") (pin "20-A6/TX5/LRCLK1") (pinfunction "20-A6/TX5/LRCLK1_20-A6/TX5/LRCLK1") (pintype "bidirectional"))
    )
    (net (code "97") (name "unconnected-(TEENSY4.1-Pad21-A7{slash}RX5{slash}BCLK1)") (class "Default")
      (node (ref "TEENSY4.1") (pin "21-A7/RX5/BCLK1") (pinfunction "21-A7/RX5/BCLK1_21-A7/RX5/BCLK1") (pintype "bidirectional"))
    )
    (net (code "98") (name "unconnected-(TEENSY4.1-Pad23-A9{slash}CRX1{slash}MCLK1)") (class "Default")
      (node (ref "TEENSY4.1") (pin "23-A9/CRX1/MCLK1") (pinfunction "23-A9/CRX1/MCLK1_23-A9/CRX1/MCLK1") (pintype "bidirectional"))
    )
    (net (code "99") (name "unconnected-(TEENSY4.1-Pad24-A10{slash}TX6{slash}SCL2)") (class "Default")
      (node (ref "TEENSY4.1") (pin "24-A10/TX6/SCL2") (pinfunction "24-A10/TX6/SCL2_24-A10/TX6/SCL2") (pintype "bidirectional"))
    )
    (net (code "100") (name "unconnected-(TEENSY4.1-Pad25-A11{slash}RX6{slash}SDA2)") (class "Default")
      (node (ref "TEENSY4.1") (pin "25-A11/RX6/SDA2") (pinfunction "25-A11/RX6/SDA2_25-A11/RX6/SDA2") (pintype "bidirectional"))
    )
    (net (code "101") (name "unconnected-(TEENSY4.1-Pad28-RX7)") (class "Default")
      (node (ref "TEENSY4.1") (pin "28-RX7") (pinfunction "28-RX7_28-RX7") (pintype "bidirectional"))
    )
    (net (code "102") (name "unconnected-(TEENSY4.1-Pad29-TX7)") (class "Default")
      (node (ref "TEENSY4.1") (pin "29-TX7") (pinfunction "29-TX7_29-TX7") (pintype "bidirectional"))
    )
    (net (code "103") (name "unconnected-(TEENSY4.1-PadD+)") (class "Default")
      (node (ref "TEENSY4.1") (pin "D+") (pinfunction "D+_D+") (pintype "bidirectional"))
    )
    (net (code "104") (name "unconnected-(TEENSY4.1-PadD-)") (class "Default")
      (node (ref "TEENSY4.1") (pin "D-") (pinfunction "D-_D-") (pintype "bidirectional"))
    )
    (net (code "105") (name "unconnected-(TEENSY4.1-PadDM)") (class "Default")
      (node (ref "TEENSY4.1") (pin "DM") (pinfunction "DM_DM") (pintype "bidirectional"))
    )
    (net (code "106") (name "unconnected-(TEENSY4.1-PadDP)") (class "Default")
      (node (ref "TEENSY4.1") (pin "DP") (pinfunction "DP_DP") (pintype "bidirectional"))
    )
    (net (code "107") (name "unconnected-(TEENSY4.1-PadG)") (class "Default")
      (node (ref "TEENSY4.1") (pin "G") (pinfunction "G_G") (pintype "bidirectional"))
    )
    (net (code "108") (name "unconnected-(TEENSY4.1-PadLED)") (class "Default")
      (node (ref "TEENSY4.1") (pin "LED") (pinfunction "LED_LED") (pintype "bidirectional"))
    )
    (net (code "109") (name "unconnected-(TEENSY4.1-PadON{slash}OFF)") (class "Default")
      (node (ref "TEENSY4.1") (pin "ON/OFF") (pinfunction "ON/OFF_ON/OFF") (pintype "bidirectional"))
    )
    (net (code "110") (name "unconnected-(TEENSY4.1-PadPROGRAM)") (class "Default")
      (node (ref "TEENSY4.1") (pin "PROGRAM") (pinfunction "PROGRAM_PROGRAM") (pintype "bidirectional"))
    )
    (net (code "111") (name "unconnected-(TEENSY4.1-PadR+)") (class "Default")
      (node (ref "TEENSY4.1") (pin "R+") (pinfunction "R+_R+") (pintype "bidirectional"))
    )
    (net (code "112") (name "unconnected-(TEENSY4.1-PadR-)") (class "Default")
      (node (ref "TEENSY4.1") (pin "R-") (pinfunction "R-_R-") (pintype "bidirectional"))
    )
    (net (code "113") (name "unconnected-(TEENSY4.1-PadT+)") (class "Default")
      (node (ref "TEENSY4.1") (pin "T+") (pinfunction "T+_T+") (pintype "bidirectional"))
    )
    (net (code "114") (name "unconnected-(TEENSY4.1-PadT-)") (class "Default")
      (node (ref "TEENSY4.1") (pin "T-") (pinfunction "T-_T-") (pintype "bidirectional"))
    )
    (net (code "115") (name "unconnected-(TEENSY4.1-PadVBAT)") (class "Default")
      (node (ref "TEENSY4.1") (pin "VBAT") (pinfunction "VBAT_VBAT") (pintype "bidirectional"))
    )
    (net (code "116") (name "unconnected-(TEENSY4.1-PadVUSB)") (class "Default")
      (node (ref "TEENSY4.1") (pin "VUSB") (pinfunction "VUSB_VUSB") (pintype "bidirectional"))
    )
    (net (code "117") (name "unconnected-(U1-Pad3VO)") (class "Default")
      (node (ref "U1") (pin "3VO") (pinfunction "3VO_3VO") (pintype "bidirectional"))
    )
    (net (code "118") (name "unconnected-(U1-PadCS)") (class "Default")
      (node (ref "U1") (pin "CS") (pinfunction "CS_CS") (pintype "bidirectional"))
    )
    (net (code "119") (name "unconnected-(U1-PadSDO)") (class "Default")
      (node (ref "U1") (pin "SDO") (pinfunction "SDO_SDO") (pintype "bidirectional"))
    )
  )
)
